# Main_Board.net
KiCad netlist of a schematic drawn in Altium Designer
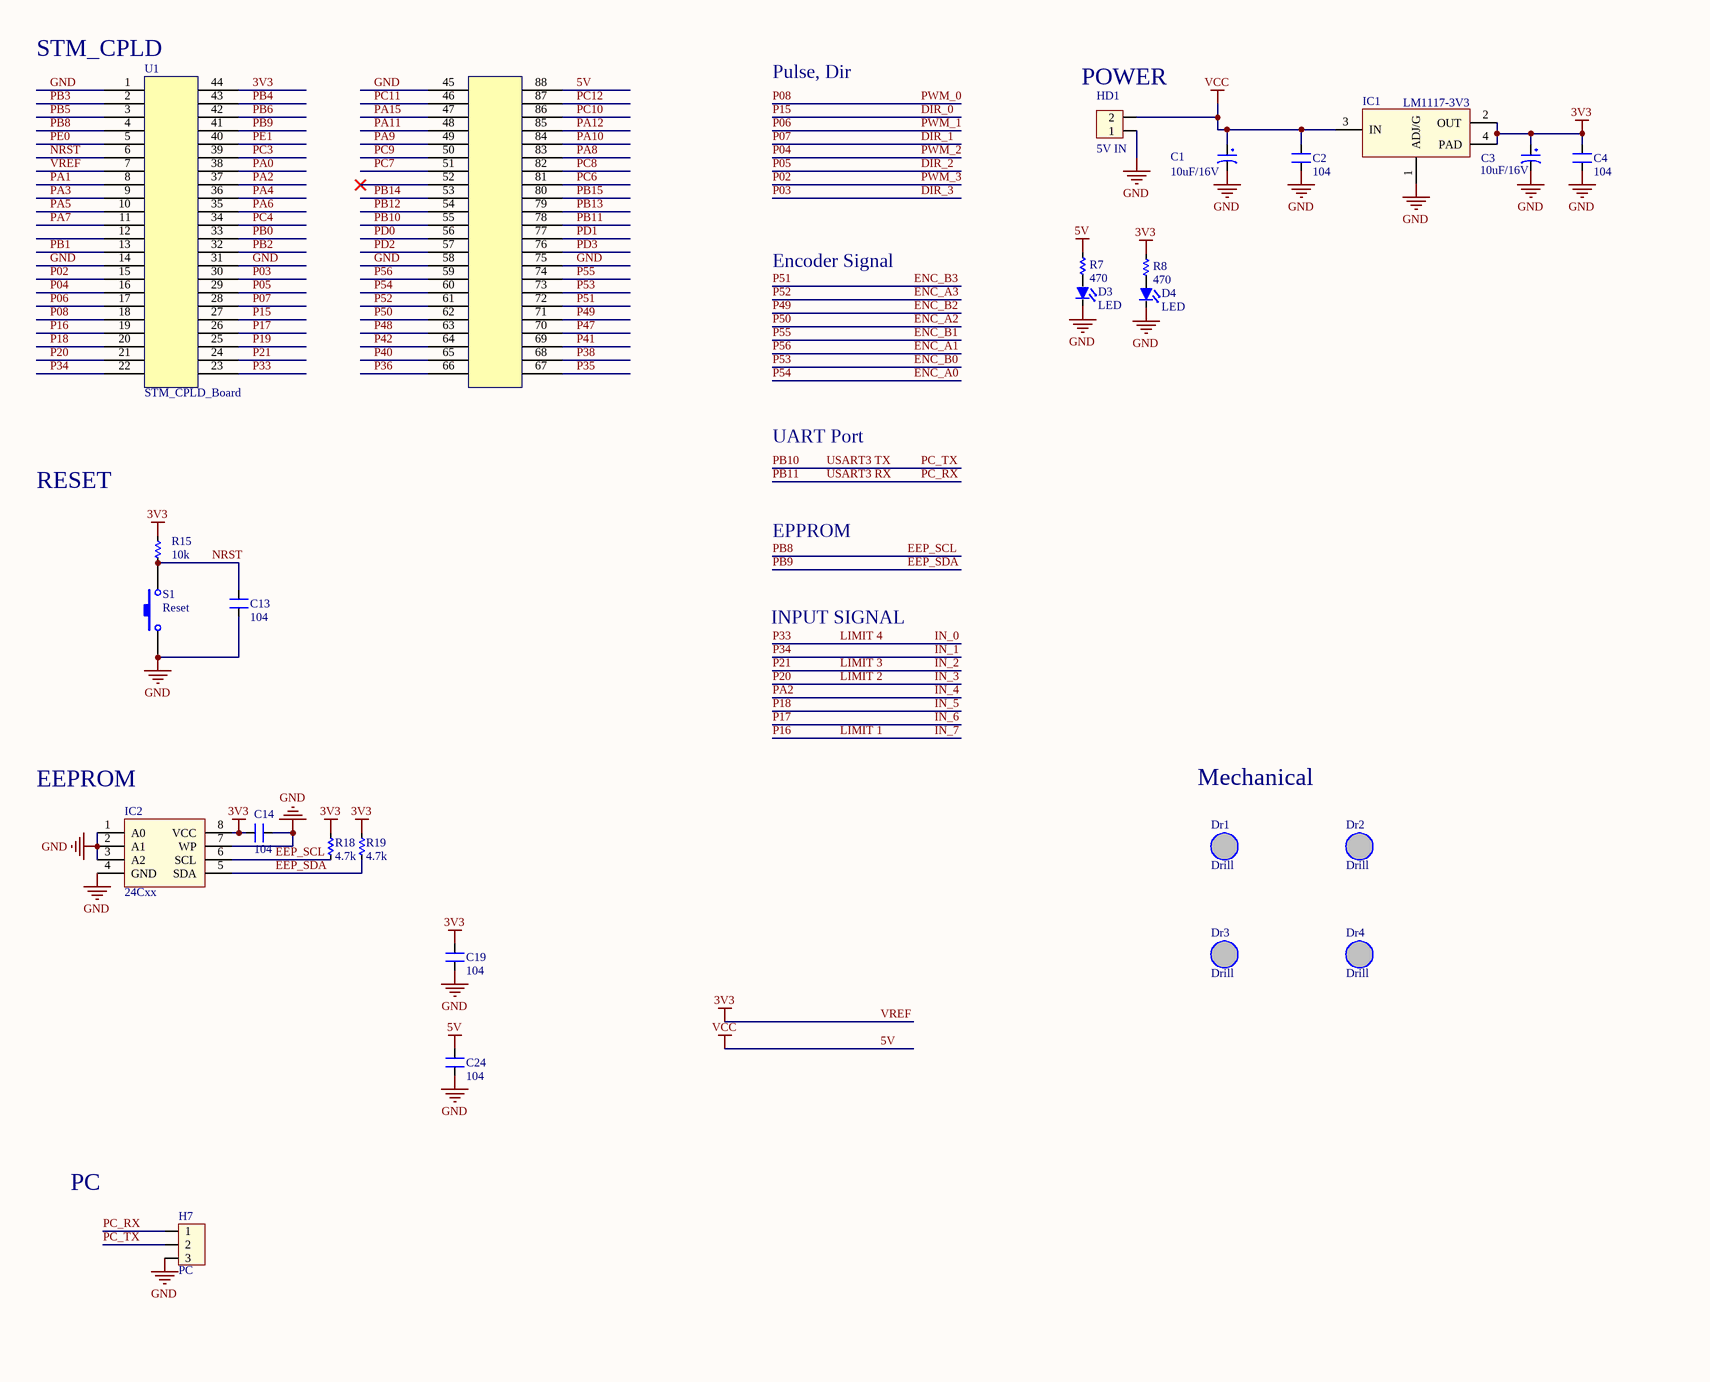
[diagram p0: Main_Board.SchDoc, top left]
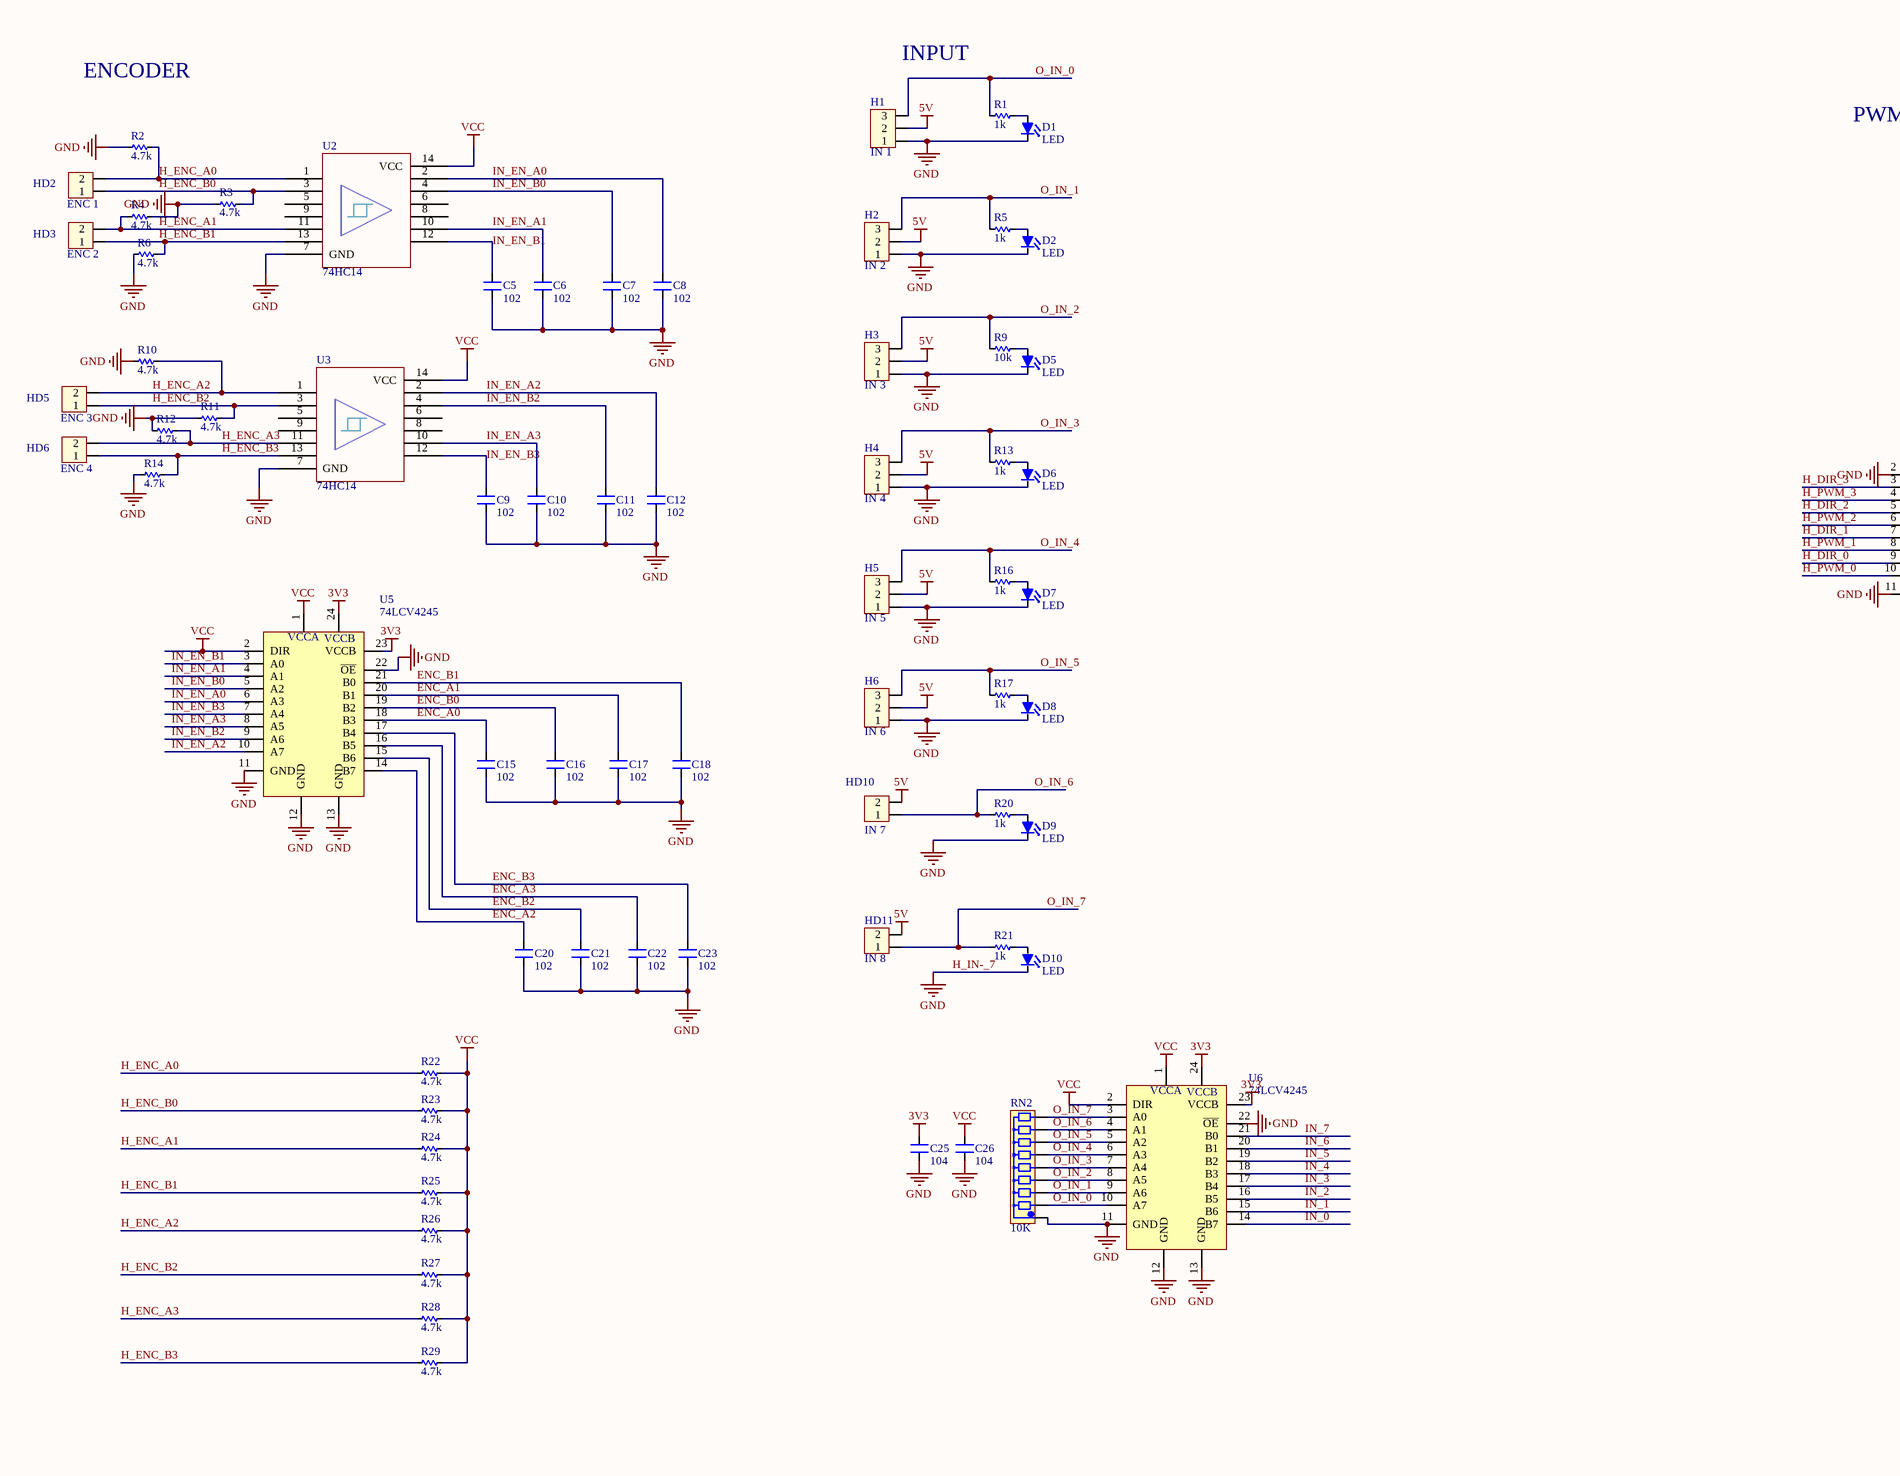
[diagram p1: Main_Board.SchDoc, top middle]
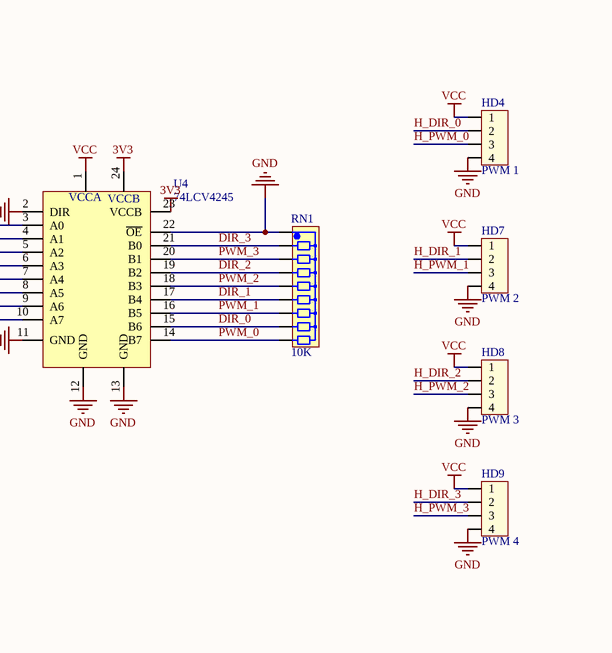
[diagram p2: Main_Board.SchDoc, top right]
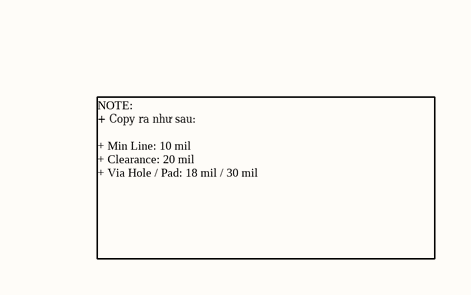
[diagram p3: Main_Board.SchDoc, bottom right]

(export (version "E")
  (design (tool "Eeschema 10.0.6"))
  (components
    (comp (ref "C1")
      (value "10uF/16V")
      (footprint "CAP_ALU_B")
      (description "C 47uF/50V , 220uF/16V")
      (libsource (lib "Main_Board") (part "CP2"))
    )
    (comp (ref "C2")
      (value "104")
      (footprint "CAP-SM-0805")
      (description "Ceramic Capacitor SMD")
      (libsource (lib "Main_Board") (part "CAP_SM_0805"))
    )
    (comp (ref "C3")
      (value "10uF/16V")
      (footprint "CAP_ALU_B")
      (description "C 47uF/50V , 220uF/16V")
      (libsource (lib "Main_Board") (part "CP2"))
    )
    (comp (ref "C4")
      (value "104")
      (footprint "CAP-SM-0805")
      (description "Ceramic Capacitor SMD")
      (libsource (lib "Main_Board") (part "CAP_SM_0805"))
    )
    (comp (ref "C5")
      (value "102")
      (footprint "CAP-SM-0805")
      (description "Ceramic Capacitor SMD")
      (libsource (lib "Main_Board") (part "CAP_SM_0805"))
    )
    (comp (ref "C6")
      (value "102")
      (footprint "CAP-SM-0805")
      (description "Ceramic Capacitor SMD")
      (libsource (lib "Main_Board") (part "CAP_SM_0805"))
    )
    (comp (ref "C7")
      (value "102")
      (footprint "CAP-SM-0805")
      (description "Ceramic Capacitor SMD")
      (libsource (lib "Main_Board") (part "CAP_SM_0805"))
    )
    (comp (ref "C8")
      (value "102")
      (footprint "CAP-SM-0805")
      (description "Ceramic Capacitor SMD")
      (libsource (lib "Main_Board") (part "CAP_SM_0805"))
    )
    (comp (ref "C9")
      (value "102")
      (footprint "CAP-SM-0805")
      (description "Ceramic Capacitor SMD")
      (libsource (lib "Main_Board") (part "CAP_SM_0805"))
    )
    (comp (ref "C10")
      (value "102")
      (footprint "CAP-SM-0805")
      (description "Ceramic Capacitor SMD")
      (libsource (lib "Main_Board") (part "CAP_SM_0805"))
    )
    (comp (ref "C11")
      (value "102")
      (footprint "CAP-SM-0805")
      (description "Ceramic Capacitor SMD")
      (libsource (lib "Main_Board") (part "CAP_SM_0805"))
    )
    (comp (ref "C12")
      (value "102")
      (footprint "CAP-SM-0805")
      (description "Ceramic Capacitor SMD")
      (libsource (lib "Main_Board") (part "CAP_SM_0805"))
    )
    (comp (ref "C13")
      (value "104")
      (footprint "CAP-SM-0805")
      (description "Ceramic Capacitor SMD")
      (libsource (lib "Main_Board") (part "CAP_SM_0805"))
    )
    (comp (ref "C14")
      (value "104")
      (footprint "CAP-SM-0805")
      (description "Ceramic Capacitor SMD")
      (libsource (lib "Main_Board") (part "CAP_SM_0805"))
    )
    (comp (ref "C15")
      (value "102")
      (footprint "CAP-SM-0805")
      (description "Ceramic Capacitor SMD")
      (libsource (lib "Main_Board") (part "CAP_SM_0805"))
    )
    (comp (ref "C16")
      (value "102")
      (footprint "CAP-SM-0805")
      (description "Ceramic Capacitor SMD")
      (libsource (lib "Main_Board") (part "CAP_SM_0805"))
    )
    (comp (ref "C17")
      (value "102")
      (footprint "CAP-SM-0805")
      (description "Ceramic Capacitor SMD")
      (libsource (lib "Main_Board") (part "CAP_SM_0805"))
    )
    (comp (ref "C18")
      (value "102")
      (footprint "CAP-SM-0805")
      (description "Ceramic Capacitor SMD")
      (libsource (lib "Main_Board") (part "CAP_SM_0805"))
    )
    (comp (ref "C19")
      (value "104")
      (footprint "CAP-SM-0805")
      (description "Ceramic Capacitor SMD")
      (libsource (lib "Main_Board") (part "CAP_SM_0805"))
    )
    (comp (ref "C20")
      (value "102")
      (footprint "CAP-SM-0805")
      (description "Ceramic Capacitor SMD")
      (libsource (lib "Main_Board") (part "CAP_SM_0805"))
    )
    (comp (ref "C21")
      (value "102")
      (footprint "CAP-SM-0805")
      (description "Ceramic Capacitor SMD")
      (libsource (lib "Main_Board") (part "CAP_SM_0805"))
    )
    (comp (ref "C22")
      (value "102")
      (footprint "CAP-SM-0805")
      (description "Ceramic Capacitor SMD")
      (libsource (lib "Main_Board") (part "CAP_SM_0805"))
    )
    (comp (ref "C23")
      (value "102")
      (footprint "CAP-SM-0805")
      (description "Ceramic Capacitor SMD")
      (libsource (lib "Main_Board") (part "CAP_SM_0805"))
    )
    (comp (ref "C24")
      (value "104")
      (footprint "CAP-SM-0805")
      (description "Ceramic Capacitor SMD")
      (libsource (lib "Main_Board") (part "CAP_SM_0805"))
    )
    (comp (ref "C25")
      (value "104")
      (footprint "CAP-SM-0805")
      (description "Ceramic Capacitor SMD")
      (libsource (lib "Main_Board") (part "CAP_SM_0805"))
    )
    (comp (ref "C26")
      (value "104")
      (footprint "CAP-SM-0805")
      (description "Ceramic Capacitor SMD")
      (libsource (lib "Main_Board") (part "CAP_SM_0805"))
    )
    (comp (ref "D1")
      (value "LED")
      (footprint "LED_0805_Blue")
      (description "LED SMD")
      (libsource (lib "Main_Board") (part "LED_SMD"))
    )
    (comp (ref "D2")
      (value "LED")
      (footprint "LED_0805_Blue")
      (description "LED SMD")
      (libsource (lib "Main_Board") (part "LED_SMD"))
    )
    (comp (ref "D3")
      (value "LED")
      (footprint "LED_0805_Blue")
      (description "LED SMD")
      (libsource (lib "Main_Board") (part "LED_SMD"))
    )
    (comp (ref "D4")
      (value "LED")
      (footprint "LED_0805_Blue")
      (description "LED SMD")
      (libsource (lib "Main_Board") (part "LED_SMD"))
    )
    (comp (ref "D5")
      (value "LED")
      (footprint "LED_0805_Blue")
      (description "LED SMD")
      (libsource (lib "Main_Board") (part "LED_SMD"))
    )
    (comp (ref "D6")
      (value "LED")
      (footprint "LED_0805_Blue")
      (description "LED SMD")
      (libsource (lib "Main_Board") (part "LED_SMD"))
    )
    (comp (ref "D7")
      (value "LED")
      (footprint "LED_0805_Blue")
      (description "LED SMD")
      (libsource (lib "Main_Board") (part "LED_SMD"))
    )
    (comp (ref "D8")
      (value "LED")
      (footprint "LED_0805_Blue")
      (description "LED SMD")
      (libsource (lib "Main_Board") (part "LED_SMD"))
    )
    (comp (ref "D9")
      (value "LED")
      (footprint "LED_0805_Blue")
      (description "LED SMD")
      (libsource (lib "Main_Board") (part "LED_SMD"))
    )
    (comp (ref "D10")
      (value "LED")
      (footprint "LED_0805_Blue")
      (description "LED SMD")
      (libsource (lib "Main_Board") (part "LED_SMD"))
    )
    (comp (ref "Dr1")
      (value "Drill")
      (footprint "Drill 3mm")
      (description "Drill 3mm")
      (libsource (lib "Main_Board") (part "Drill 3mm"))
    )
    (comp (ref "Dr2")
      (value "Drill")
      (footprint "Drill 3mm")
      (description "Drill 3mm")
      (libsource (lib "Main_Board") (part "Drill 3mm"))
    )
    (comp (ref "Dr3")
      (value "Drill")
      (footprint "Drill 3mm")
      (description "Drill 3mm")
      (libsource (lib "Main_Board") (part "Drill 3mm"))
    )
    (comp (ref "Dr4")
      (value "Drill")
      (footprint "Drill 3mm")
      (description "Drill 3mm")
      (libsource (lib "Main_Board") (part "Drill 3mm"))
    )
    (comp (ref "H1")
      (value "IN 1")
      (footprint "Header White 3")
      (description "Connector 3")
      (libsource (lib "Main_Board") (part "Header white 3"))
    )
    (comp (ref "H2")
      (value "IN 2")
      (footprint "Header White 3")
      (description "Connector 3")
      (libsource (lib "Main_Board") (part "Header white 3"))
    )
    (comp (ref "H3")
      (value "IN 3")
      (footprint "Header White 3")
      (description "Connector 3")
      (libsource (lib "Main_Board") (part "Header white 3"))
    )
    (comp (ref "H4")
      (value "IN 4")
      (footprint "Header White 3")
      (description "Connector 3")
      (libsource (lib "Main_Board") (part "Header white 3"))
    )
    (comp (ref "H5")
      (value "IN 5")
      (footprint "Header White 3")
      (description "Connector 3")
      (libsource (lib "Main_Board") (part "Header white 3"))
    )
    (comp (ref "H6")
      (value "IN 6")
      (footprint "Header White 3")
      (description "Connector 3")
      (libsource (lib "Main_Board") (part "Header white 3"))
    )
    (comp (ref "H7")
      (value "PC")
      (footprint "Header White 3")
      (description "Connector 3")
      (libsource (lib "") (part "Header white 3_1"))
    )
    (comp (ref "HD1")
      (value "5V IN")
      (footprint "Domino 2")
      (description "Domino 2 200mil")
      (libsource (lib "Main_Board") (part "Domino 2"))
    )
    (comp (ref "HD2")
      (value "ENC 1")
      (footprint "Domino 2")
      (description "Domino 2 200mil")
      (libsource (lib "Main_Board") (part "Domino 2"))
    )
    (comp (ref "HD3")
      (value "ENC 2")
      (footprint "Domino 2")
      (description "Domino 2 200mil")
      (libsource (lib "Main_Board") (part "Domino 2"))
    )
    (comp (ref "HD4")
      (value "PWM 1")
      (footprint "Domino 4")
      (description "Domino 4 200mil")
      (libsource (lib "Main_Board") (part "Domino 4"))
    )
    (comp (ref "HD5")
      (value "ENC 3")
      (footprint "Domino 2")
      (description "Domino 2 200mil")
      (libsource (lib "Main_Board") (part "Domino 2"))
    )
    (comp (ref "HD6")
      (value "ENC 4")
      (footprint "Domino 2")
      (description "Domino 2 200mil")
      (libsource (lib "Main_Board") (part "Domino 2"))
    )
    (comp (ref "HD7")
      (value "PWM 2")
      (footprint "Domino 4")
      (description "Domino 4 200mil")
      (libsource (lib "Main_Board") (part "Domino 4"))
    )
    (comp (ref "HD8")
      (value "PWM 3")
      (footprint "Domino 4")
      (description "Domino 4 200mil")
      (libsource (lib "Main_Board") (part "Domino 4"))
    )
    (comp (ref "HD9")
      (value "PWM 4")
      (footprint "Domino 4")
      (description "Domino 4 200mil")
      (libsource (lib "Main_Board") (part "Domino 4"))
    )
    (comp (ref "HD10")
      (value "IN 7")
      (footprint "Domino 2")
      (description "Domino 2 200mil")
      (libsource (lib "Main_Board") (part "Domino 2"))
    )
    (comp (ref "HD11")
      (value "IN 8")
      (footprint "Domino 2")
      (description "Domino 2 200mil")
      (libsource (lib "Main_Board") (part "Domino 2"))
    )
    (comp (ref "IC1")
      (value "LM1117-3V3")
      (footprint "SOT223-4N")
      (description "Available in 1.8V, 2.5V, 2.85V, 3.3V, 5V, and  Adjustable Versions")
      (libsource (lib "Main_Board") (part "LM1117"))
    )
    (comp (ref "IC2")
      (value "24Cxx")
      (footprint "SOIC8")
      (description "Standard 2-Wire Bus Interface Serial EEPROM")
      (fields (field (name "COPYRIGHT BY") "VanDungEvn"))
      (libsource (lib "Main_Board") (part "24Cxx"))
    )
    (comp (ref "R1")
      (value "1k")
      (footprint "RES-SM-0805")
      (description "Resistor")
      (fields
        (field (name "MANUFACTURER") "Generic Components")
        (field (name "PUBLISHER") "Altium Hobart Technology Centre")
      )
      (libsource (lib "Main_Board") (part "Res-SMD"))
    )
    (comp (ref "R2")
      (value "4.7k")
      (footprint "RES-SM-0805")
      (description "Resistor")
      (fields
        (field (name "MANUFACTURER") "Generic Components")
        (field (name "PUBLISHER") "Altium Hobart Technology Centre")
      )
      (libsource (lib "Main_Board") (part "Res-SMD"))
    )
    (comp (ref "R3")
      (value "4.7k")
      (footprint "RES-SM-0805")
      (description "Resistor")
      (fields
        (field (name "MANUFACTURER") "Generic Components")
        (field (name "PUBLISHER") "Altium Hobart Technology Centre")
      )
      (libsource (lib "Main_Board") (part "Res-SMD"))
    )
    (comp (ref "R4")
      (value "4.7k")
      (footprint "RES-SM-0805")
      (description "Resistor")
      (fields
        (field (name "MANUFACTURER") "Generic Components")
        (field (name "PUBLISHER") "Altium Hobart Technology Centre")
      )
      (libsource (lib "Main_Board") (part "Res-SMD"))
    )
    (comp (ref "R5")
      (value "1k")
      (footprint "RES-SM-0805")
      (description "Resistor")
      (fields
        (field (name "MANUFACTURER") "Generic Components")
        (field (name "PUBLISHER") "Altium Hobart Technology Centre")
      )
      (libsource (lib "Main_Board") (part "Res-SMD"))
    )
    (comp (ref "R6")
      (value "4.7k")
      (footprint "RES-SM-0805")
      (description "Resistor")
      (fields
        (field (name "MANUFACTURER") "Generic Components")
        (field (name "PUBLISHER") "Altium Hobart Technology Centre")
      )
      (libsource (lib "Main_Board") (part "Res-SMD"))
    )
    (comp (ref "R7")
      (value "470")
      (footprint "RES-SM-0805")
      (description "Resistor")
      (fields
        (field (name "MANUFACTURER") "Generic Components")
        (field (name "PUBLISHER") "Altium Hobart Technology Centre")
      )
      (libsource (lib "Main_Board") (part "Res-SMD"))
    )
    (comp (ref "R8")
      (value "470")
      (footprint "RES-SM-0805")
      (description "Resistor")
      (fields
        (field (name "MANUFACTURER") "Generic Components")
        (field (name "PUBLISHER") "Altium Hobart Technology Centre")
      )
      (libsource (lib "Main_Board") (part "Res-SMD"))
    )
    (comp (ref "R9")
      (value "10k")
      (footprint "RES-SM-0805")
      (description "Resistor")
      (fields
        (field (name "MANUFACTURER") "Generic Components")
        (field (name "PUBLISHER") "Altium Hobart Technology Centre")
      )
      (libsource (lib "Main_Board") (part "Res-SMD"))
    )
    (comp (ref "R10")
      (value "4.7k")
      (footprint "RES-SM-0805")
      (description "Resistor")
      (fields
        (field (name "MANUFACTURER") "Generic Components")
        (field (name "PUBLISHER") "Altium Hobart Technology Centre")
      )
      (libsource (lib "Main_Board") (part "Res-SMD"))
    )
    (comp (ref "R11")
      (value "4.7k")
      (footprint "RES-SM-0805")
      (description "Resistor")
      (fields
        (field (name "MANUFACTURER") "Generic Components")
        (field (name "PUBLISHER") "Altium Hobart Technology Centre")
      )
      (libsource (lib "Main_Board") (part "Res-SMD"))
    )
    (comp (ref "R12")
      (value "4.7k")
      (footprint "RES-SM-0805")
      (description "Resistor")
      (fields
        (field (name "MANUFACTURER") "Generic Components")
        (field (name "PUBLISHER") "Altium Hobart Technology Centre")
      )
      (libsource (lib "Main_Board") (part "Res-SMD"))
    )
    (comp (ref "R13")
      (value "1k")
      (footprint "RES-SM-0805")
      (description "Resistor")
      (fields
        (field (name "MANUFACTURER") "Generic Components")
        (field (name "PUBLISHER") "Altium Hobart Technology Centre")
      )
      (libsource (lib "Main_Board") (part "Res-SMD"))
    )
    (comp (ref "R14")
      (value "4.7k")
      (footprint "RES-SM-0805")
      (description "Resistor")
      (fields
        (field (name "MANUFACTURER") "Generic Components")
        (field (name "PUBLISHER") "Altium Hobart Technology Centre")
      )
      (libsource (lib "Main_Board") (part "Res-SMD"))
    )
    (comp (ref "R15")
      (value "10k")
      (footprint "RES-SM-0805")
      (description "Resistor")
      (fields
        (field (name "MANUFACTURER") "Generic Components")
        (field (name "PUBLISHER") "Altium Hobart Technology Centre")
      )
      (libsource (lib "Main_Board") (part "Res-SMD"))
    )
    (comp (ref "R16")
      (value "1k")
      (footprint "RES-SM-0805")
      (description "Resistor")
      (fields
        (field (name "MANUFACTURER") "Generic Components")
        (field (name "PUBLISHER") "Altium Hobart Technology Centre")
      )
      (libsource (lib "Main_Board") (part "Res-SMD"))
    )
    (comp (ref "R17")
      (value "1k")
      (footprint "RES-SM-0805")
      (description "Resistor")
      (fields
        (field (name "MANUFACTURER") "Generic Components")
        (field (name "PUBLISHER") "Altium Hobart Technology Centre")
      )
      (libsource (lib "Main_Board") (part "Res-SMD"))
    )
    (comp (ref "R18")
      (value "4.7k")
      (footprint "RES-SM-0805")
      (description "Resistor")
      (fields
        (field (name "MANUFACTURER") "Generic Components")
        (field (name "PUBLISHER") "Altium Hobart Technology Centre")
      )
      (libsource (lib "Main_Board") (part "Res-SMD"))
    )
    (comp (ref "R19")
      (value "4.7k")
      (footprint "RES-SM-0805")
      (description "Resistor")
      (fields
        (field (name "MANUFACTURER") "Generic Components")
        (field (name "PUBLISHER") "Altium Hobart Technology Centre")
      )
      (libsource (lib "Main_Board") (part "Res-SMD"))
    )
    (comp (ref "R20")
      (value "1k")
      (footprint "RES-SM-0805")
      (description "Resistor")
      (fields
        (field (name "MANUFACTURER") "Generic Components")
        (field (name "PUBLISHER") "Altium Hobart Technology Centre")
      )
      (libsource (lib "Main_Board") (part "Res-SMD"))
    )
    (comp (ref "R21")
      (value "1k")
      (footprint "RES-SM-0805")
      (description "Resistor")
      (fields
        (field (name "MANUFACTURER") "Generic Components")
        (field (name "PUBLISHER") "Altium Hobart Technology Centre")
      )
      (libsource (lib "Main_Board") (part "Res-SMD"))
    )
    (comp (ref "R22")
      (value "4.7k")
      (footprint "RES-SM-0805")
      (description "Resistor")
      (fields
        (field (name "MANUFACTURER") "Generic Components")
        (field (name "PUBLISHER") "Altium Hobart Technology Centre")
      )
      (libsource (lib "Main_Board") (part "Res-SMD"))
    )
    (comp (ref "R23")
      (value "4.7k")
      (footprint "RES-SM-0805")
      (description "Resistor")
      (fields
        (field (name "MANUFACTURER") "Generic Components")
        (field (name "PUBLISHER") "Altium Hobart Technology Centre")
      )
      (libsource (lib "Main_Board") (part "Res-SMD"))
    )
    (comp (ref "R24")
      (value "4.7k")
      (footprint "RES-SM-0805")
      (description "Resistor")
      (fields
        (field (name "MANUFACTURER") "Generic Components")
        (field (name "PUBLISHER") "Altium Hobart Technology Centre")
      )
      (libsource (lib "Main_Board") (part "Res-SMD"))
    )
    (comp (ref "R25")
      (value "4.7k")
      (footprint "RES-SM-0805")
      (description "Resistor")
      (fields
        (field (name "MANUFACTURER") "Generic Components")
        (field (name "PUBLISHER") "Altium Hobart Technology Centre")
      )
      (libsource (lib "Main_Board") (part "Res-SMD"))
    )
    (comp (ref "R26")
      (value "4.7k")
      (footprint "RES-SM-0805")
      (description "Resistor")
      (fields
        (field (name "MANUFACTURER") "Generic Components")
        (field (name "PUBLISHER") "Altium Hobart Technology Centre")
      )
      (libsource (lib "Main_Board") (part "Res-SMD"))
    )
    (comp (ref "R27")
      (value "4.7k")
      (footprint "RES-SM-0805")
      (description "Resistor")
      (fields
        (field (name "MANUFACTURER") "Generic Components")
        (field (name "PUBLISHER") "Altium Hobart Technology Centre")
      )
      (libsource (lib "Main_Board") (part "Res-SMD"))
    )
    (comp (ref "R28")
      (value "4.7k")
      (footprint "RES-SM-0805")
      (description "Resistor")
      (fields
        (field (name "MANUFACTURER") "Generic Components")
        (field (name "PUBLISHER") "Altium Hobart Technology Centre")
      )
      (libsource (lib "Main_Board") (part "Res-SMD"))
    )
    (comp (ref "R29")
      (value "4.7k")
      (footprint "RES-SM-0805")
      (description "Resistor")
      (fields
        (field (name "MANUFACTURER") "Generic Components")
        (field (name "PUBLISHER") "Altium Hobart Technology Centre")
      )
      (libsource (lib "Main_Board") (part "Res-SMD"))
    )
    (comp (ref "RN1")
      (value "10K")
      (footprint "RN8")
      (description "Resistor 8 (Thanh)")
      (libsource (lib "Main_Board") (part "RN8"))
    )
    (comp (ref "RN2")
      (value "10K")
      (footprint "RN8")
      (description "Resistor 8 (Thanh)")
      (libsource (lib "") (part "RN8_1"))
    )
    (comp (ref "S1")
      (value "Reset")
      (footprint "SW2")
      (description "Switch button 2 pin")
      (libsource (lib "Main_Board") (part "SW - 2Pin"))
    )
    (comp (ref "U1")
      (value "STM_CPLD_Board")
      (footprint "STM_CPLD_Board")
      (description "STM32f4 and Max2 570 on one board")
      (libsource (lib "Main_Board") (part "STM_CPLD_Board"))
    )
    (comp (ref "U2")
      (value "74HC14")
      (footprint "SO14-150mil")
      (description "Hex Inverters With SCHMITT-TRIGGER Inputs")
      (libsource (lib "Main_Board") (part "74HC14"))
    )
    (comp (ref "U3")
      (value "74HC14")
      (footprint "SO14-150mil")
      (description "Hex Inverters With SCHMITT-TRIGGER Inputs")
      (libsource (lib "Main_Board") (part "74HC14"))
    )
    (comp (ref "U4")
      (value "74LCV4245")
      (footprint "SOIC24 - wide")
      (description "Octal dual supply translating transceiver; 3-state")
      (libsource (lib "Main_Board") (part "74LCV4245"))
    )
    (comp (ref "U5")
      (value "74LCV4245")
      (footprint "SOIC24 - wide")
      (description "Octal dual supply translating transceiver; 3-state")
      (libsource (lib "Main_Board") (part "74LCV4245"))
    )
    (comp (ref "U6")
      (value "74LCV4245")
      (footprint "SOIC24 - wide")
      (description "Octal dual supply translating transceiver; 3-state")
      (libsource (lib "Main_Board") (part "74LCV4245"))
    )
  )
  (nets
    (net (code "1") (name "/DIR_0") (class "Default")
      (node (ref "RN1") (pin "8") (pinfunction "8_8") (pintype "passive"))
      (node (ref "U1") (pin "27") (pinfunction "27_27") (pintype "passive"))
      (node (ref "U4") (pin "15") (pinfunction "B6_15") (pintype "passive"))
    )
    (net (code "2") (name "/DIR_1") (class "Default")
      (node (ref "RN1") (pin "6") (pinfunction "6_6") (pintype "passive"))
      (node (ref "U1") (pin "28") (pinfunction "28_28") (pintype "passive"))
      (node (ref "U4") (pin "17") (pinfunction "B4_17") (pintype "passive"))
    )
    (net (code "3") (name "/DIR_2") (class "Default")
      (node (ref "RN1") (pin "4") (pinfunction "4_4") (pintype "passive"))
      (node (ref "U1") (pin "29") (pinfunction "29_29") (pintype "passive"))
      (node (ref "U4") (pin "19") (pinfunction "B2_19") (pintype "passive"))
    )
    (net (code "4") (name "/DIR_3") (class "Default")
      (node (ref "RN1") (pin "2") (pinfunction "2_2") (pintype "passive"))
      (node (ref "U1") (pin "30") (pinfunction "30_30") (pintype "passive"))
      (node (ref "U4") (pin "21") (pinfunction "B0_21") (pintype "passive"))
    )
    (net (code "5") (name "/EEP_SCL") (class "Default")
      (node (ref "IC2") (pin "6") (pinfunction "SCL_6") (pintype "passive"))
      (node (ref "R18") (pin "1") (pinfunction "1_1") (pintype "passive"))
      (node (ref "U1") (pin "4") (pinfunction "4_4") (pintype "passive"))
    )
    (net (code "6") (name "/EEP_SDA") (class "Default")
      (node (ref "IC2") (pin "5") (pinfunction "SDA_5") (pintype "passive"))
      (node (ref "R19") (pin "2") (pinfunction "2_2") (pintype "passive"))
      (node (ref "U1") (pin "41") (pinfunction "41_41") (pintype "passive"))
    )
    (net (code "7") (name "/ENC_A0") (class "Default")
      (node (ref "C15") (pin "2") (pinfunction "2_2") (pintype "passive"))
      (node (ref "U1") (pin "60") (pinfunction "60_60") (pintype "passive"))
      (node (ref "U5") (pin "18") (pinfunction "B3_18") (pintype "passive"))
    )
    (net (code "8") (name "/ENC_A1") (class "Default")
      (node (ref "C17") (pin "2") (pinfunction "2_2") (pintype "passive"))
      (node (ref "U1") (pin "59") (pinfunction "59_59") (pintype "passive"))
      (node (ref "U5") (pin "20") (pinfunction "B1_20") (pintype "passive"))
    )
    (net (code "9") (name "/ENC_A2") (class "Default")
      (node (ref "C20") (pin "2") (pinfunction "2_2") (pintype "passive"))
      (node (ref "U1") (pin "62") (pinfunction "62_62") (pintype "passive"))
      (node (ref "U5") (pin "14") (pinfunction "B7_14") (pintype "passive"))
    )
    (net (code "10") (name "/ENC_A3") (class "Default")
      (node (ref "C22") (pin "2") (pinfunction "2_2") (pintype "passive"))
      (node (ref "U1") (pin "61") (pinfunction "61_61") (pintype "passive"))
      (node (ref "U5") (pin "16") (pinfunction "B5_16") (pintype "passive"))
    )
    (net (code "11") (name "/ENC_B0") (class "Default")
      (node (ref "C16") (pin "2") (pinfunction "2_2") (pintype "passive"))
      (node (ref "U1") (pin "73") (pinfunction "73_73") (pintype "passive"))
      (node (ref "U5") (pin "19") (pinfunction "B2_19") (pintype "passive"))
    )
    (net (code "12") (name "/ENC_B1") (class "Default")
      (node (ref "C18") (pin "2") (pinfunction "2_2") (pintype "passive"))
      (node (ref "U1") (pin "74") (pinfunction "74_74") (pintype "passive"))
      (node (ref "U5") (pin "21") (pinfunction "B0_21") (pintype "passive"))
    )
    (net (code "13") (name "/ENC_B2") (class "Default")
      (node (ref "C21") (pin "2") (pinfunction "2_2") (pintype "passive"))
      (node (ref "U1") (pin "71") (pinfunction "71_71") (pintype "passive"))
      (node (ref "U5") (pin "15") (pinfunction "B6_15") (pintype "passive"))
    )
    (net (code "14") (name "/ENC_B3") (class "Default")
      (node (ref "C23") (pin "2") (pinfunction "2_2") (pintype "passive"))
      (node (ref "U1") (pin "72") (pinfunction "72_72") (pintype "passive"))
      (node (ref "U5") (pin "17") (pinfunction "B4_17") (pintype "passive"))
    )
    (net (code "15") (name "/H_DIR_0") (class "Default")
      (node (ref "HD4") (pin "2") (pinfunction "2_2") (pintype "passive"))
      (node (ref "U4") (pin "9") (pinfunction "A6_9") (pintype "passive"))
    )
    (net (code "16") (name "/H_DIR_1") (class "Default")
      (node (ref "HD7") (pin "2") (pinfunction "2_2") (pintype "passive"))
      (node (ref "U4") (pin "7") (pinfunction "A4_7") (pintype "passive"))
    )
    (net (code "17") (name "/H_DIR_2") (class "Default")
      (node (ref "HD8") (pin "2") (pinfunction "2_2") (pintype "passive"))
      (node (ref "U4") (pin "5") (pinfunction "A2_5") (pintype "passive"))
    )
    (net (code "18") (name "/H_DIR_3") (class "Default")
      (node (ref "HD9") (pin "2") (pinfunction "2_2") (pintype "passive"))
      (node (ref "U4") (pin "3") (pinfunction "A0_3") (pintype "passive"))
    )
    (net (code "19") (name "/H_ENC_A0") (class "Default")
      (node (ref "HD2") (pin "2") (pinfunction "2_2") (pintype "passive"))
      (node (ref "R2") (pin "1") (pinfunction "1_1") (pintype "passive"))
      (node (ref "R22") (pin "1") (pinfunction "1_1") (pintype "passive"))
      (node (ref "U2") (pin "1") (pintype "passive"))
    )
    (net (code "20") (name "/H_ENC_A1") (class "Default")
      (node (ref "HD3") (pin "2") (pinfunction "2_2") (pintype "passive"))
      (node (ref "R24") (pin "1") (pinfunction "1_1") (pintype "passive"))
      (node (ref "R4") (pin "2") (pinfunction "2_2") (pintype "passive"))
      (node (ref "U2") (pin "11") (pinfunction "10_11") (pintype "passive"))
    )
    (net (code "21") (name "/H_ENC_A2") (class "Default")
      (node (ref "HD5") (pin "2") (pinfunction "2_2") (pintype "passive"))
      (node (ref "R10") (pin "1") (pinfunction "1_1") (pintype "passive"))
      (node (ref "R26") (pin "1") (pinfunction "1_1") (pintype "passive"))
      (node (ref "U3") (pin "1") (pintype "passive"))
    )
    (net (code "22") (name "/H_ENC_A3") (class "Default")
      (node (ref "HD6") (pin "2") (pinfunction "2_2") (pintype "passive"))
      (node (ref "R12") (pin "1") (pinfunction "1_1") (pintype "passive"))
      (node (ref "R28") (pin "1") (pinfunction "1_1") (pintype "passive"))
      (node (ref "U3") (pin "11") (pinfunction "10_11") (pintype "passive"))
    )
    (net (code "23") (name "/H_ENC_B0") (class "Default")
      (node (ref "HD2") (pin "1") (pinfunction "1_1") (pintype "passive"))
      (node (ref "R23") (pin "1") (pinfunction "1_1") (pintype "passive"))
      (node (ref "R3") (pin "1") (pinfunction "1_1") (pintype "passive"))
      (node (ref "U2") (pin "3") (pintype "passive"))
    )
    (net (code "24") (name "/H_ENC_B1") (class "Default")
      (node (ref "HD3") (pin "1") (pinfunction "1_1") (pintype "passive"))
      (node (ref "R25") (pin "1") (pinfunction "1_1") (pintype "passive"))
      (node (ref "R6") (pin "1") (pinfunction "1_1") (pintype "passive"))
      (node (ref "U2") (pin "13") (pinfunction "12_13") (pintype "passive"))
    )
    (net (code "25") (name "/H_ENC_B2") (class "Default")
      (node (ref "HD5") (pin "1") (pinfunction "1_1") (pintype "passive"))
      (node (ref "R11") (pin "1") (pinfunction "1_1") (pintype "passive"))
      (node (ref "R27") (pin "1") (pinfunction "1_1") (pintype "passive"))
      (node (ref "U3") (pin "3") (pintype "passive"))
    )
    (net (code "26") (name "/H_ENC_B3") (class "Default")
      (node (ref "HD6") (pin "1") (pinfunction "1_1") (pintype "passive"))
      (node (ref "R14") (pin "1") (pinfunction "1_1") (pintype "passive"))
      (node (ref "R29") (pin "1") (pinfunction "1_1") (pintype "passive"))
      (node (ref "U3") (pin "13") (pinfunction "12_13") (pintype "passive"))
    )
    (net (code "27") (name "/H_PWM_0") (class "Default")
      (node (ref "HD4") (pin "3") (pinfunction "3_3") (pintype "passive"))
      (node (ref "U4") (pin "10") (pinfunction "A7_10") (pintype "passive"))
    )
    (net (code "28") (name "/H_PWM_1") (class "Default")
      (node (ref "HD7") (pin "3") (pinfunction "3_3") (pintype "passive"))
      (node (ref "U4") (pin "8") (pinfunction "A5_8") (pintype "passive"))
    )
    (net (code "29") (name "/H_PWM_2") (class "Default")
      (node (ref "HD8") (pin "3") (pinfunction "3_3") (pintype "passive"))
      (node (ref "U4") (pin "6") (pinfunction "A3_6") (pintype "passive"))
    )
    (net (code "30") (name "/H_PWM_3") (class "Default")
      (node (ref "HD9") (pin "3") (pinfunction "3_3") (pintype "passive"))
      (node (ref "U4") (pin "4") (pinfunction "A1_4") (pintype "passive"))
    )
    (net (code "31") (name "/IN_0") (class "Default")
      (node (ref "U1") (pin "23") (pinfunction "23_23") (pintype "passive"))
      (node (ref "U6") (pin "14") (pinfunction "B7_14") (pintype "passive"))
    )
    (net (code "32") (name "/IN_1") (class "Default")
      (node (ref "U1") (pin "22") (pinfunction "22_22") (pintype "passive"))
      (node (ref "U6") (pin "15") (pinfunction "B6_15") (pintype "passive"))
    )
    (net (code "33") (name "/IN_2") (class "Default")
      (node (ref "U1") (pin "24") (pinfunction "24_24") (pintype "passive"))
      (node (ref "U6") (pin "16") (pinfunction "B5_16") (pintype "passive"))
    )
    (net (code "34") (name "/IN_3") (class "Default")
      (node (ref "U1") (pin "21") (pinfunction "21_21") (pintype "passive"))
      (node (ref "U6") (pin "17") (pinfunction "B4_17") (pintype "passive"))
    )
    (net (code "35") (name "/IN_4") (class "Default")
      (node (ref "U1") (pin "37") (pinfunction "37_37") (pintype "passive"))
      (node (ref "U6") (pin "18") (pinfunction "B3_18") (pintype "passive"))
    )
    (net (code "36") (name "/IN_5") (class "Default")
      (node (ref "U1") (pin "20") (pinfunction "20_20") (pintype "passive"))
      (node (ref "U6") (pin "19") (pinfunction "B2_19") (pintype "passive"))
    )
    (net (code "37") (name "/IN_6") (class "Default")
      (node (ref "U1") (pin "26") (pinfunction "26_26") (pintype "passive"))
      (node (ref "U6") (pin "20") (pinfunction "B1_20") (pintype "passive"))
    )
    (net (code "38") (name "/IN_7") (class "Default")
      (node (ref "U1") (pin "19") (pinfunction "19_19") (pintype "passive"))
      (node (ref "U6") (pin "21") (pinfunction "B0_21") (pintype "passive"))
    )
    (net (code "39") (name "/IN_EN_A0") (class "Default")
      (node (ref "C8") (pin "2") (pinfunction "2_2") (pintype "passive"))
      (node (ref "U2") (pin "2") (pintype "passive"))
      (node (ref "U5") (pin "6") (pinfunction "A3_6") (pintype "passive"))
    )
    (net (code "40") (name "/IN_EN_A1") (class "Default")
      (node (ref "C6") (pin "2") (pinfunction "2_2") (pintype "passive"))
      (node (ref "U2") (pin "10") (pinfunction "9_10") (pintype "passive"))
      (node (ref "U5") (pin "4") (pinfunction "A1_4") (pintype "passive"))
    )
    (net (code "41") (name "/IN_EN_A2") (class "Default")
      (node (ref "C12") (pin "2") (pinfunction "2_2") (pintype "passive"))
      (node (ref "U3") (pin "2") (pintype "passive"))
      (node (ref "U5") (pin "10") (pinfunction "A7_10") (pintype "passive"))
    )
    (net (code "42") (name "/IN_EN_A3") (class "Default")
      (node (ref "C10") (pin "2") (pinfunction "2_2") (pintype "passive"))
      (node (ref "U3") (pin "10") (pinfunction "9_10") (pintype "passive"))
      (node (ref "U5") (pin "8") (pinfunction "A5_8") (pintype "passive"))
    )
    (net (code "43") (name "/IN_EN_B0") (class "Default")
      (node (ref "C7") (pin "2") (pinfunction "2_2") (pintype "passive"))
      (node (ref "U2") (pin "4") (pintype "passive"))
      (node (ref "U5") (pin "5") (pinfunction "A2_5") (pintype "passive"))
    )
    (net (code "44") (name "/IN_EN_B1") (class "Default")
      (node (ref "C5") (pin "2") (pinfunction "2_2") (pintype "passive"))
      (node (ref "U2") (pin "12") (pinfunction "11_12") (pintype "passive"))
      (node (ref "U5") (pin "3") (pinfunction "A0_3") (pintype "passive"))
    )
    (net (code "45") (name "/IN_EN_B2") (class "Default")
      (node (ref "C11") (pin "2") (pinfunction "2_2") (pintype "passive"))
      (node (ref "U3") (pin "4") (pintype "passive"))
      (node (ref "U5") (pin "9") (pinfunction "A6_9") (pintype "passive"))
    )
    (net (code "46") (name "/IN_EN_B3") (class "Default")
      (node (ref "C9") (pin "2") (pinfunction "2_2") (pintype "passive"))
      (node (ref "U3") (pin "12") (pinfunction "11_12") (pintype "passive"))
      (node (ref "U5") (pin "7") (pinfunction "A4_7") (pintype "passive"))
    )
    (net (code "47") (name "/NRST") (class "Default")
      (node (ref "C13") (pin "1") (pinfunction "1_1") (pintype "passive"))
      (node (ref "R15") (pin "2") (pinfunction "2_2") (pintype "passive"))
      (node (ref "S1") (pin "2") (pinfunction "2_2") (pintype "passive"))
      (node (ref "U1") (pin "6") (pinfunction "6_6") (pintype "passive"))
    )
    (net (code "48") (name "/O_IN_0") (class "Default")
      (node (ref "H1") (pin "3") (pinfunction "3_3") (pintype "passive"))
      (node (ref "R1") (pin "2") (pinfunction "2_2") (pintype "passive"))
      (node (ref "RN2") (pin "2") (pinfunction "2_2") (pintype "passive"))
      (node (ref "U6") (pin "10") (pinfunction "A7_10") (pintype "passive"))
    )
    (net (code "49") (name "/O_IN_1") (class "Default")
      (node (ref "H2") (pin "3") (pinfunction "3_3") (pintype "passive"))
      (node (ref "R5") (pin "2") (pinfunction "2_2") (pintype "passive"))
      (node (ref "RN2") (pin "3") (pinfunction "3_3") (pintype "passive"))
      (node (ref "U6") (pin "9") (pinfunction "A6_9") (pintype "passive"))
    )
    (net (code "50") (name "/O_IN_2") (class "Default")
      (node (ref "H3") (pin "3") (pinfunction "3_3") (pintype "passive"))
      (node (ref "R9") (pin "2") (pinfunction "2_2") (pintype "passive"))
      (node (ref "RN2") (pin "4") (pinfunction "4_4") (pintype "passive"))
      (node (ref "U6") (pin "8") (pinfunction "A5_8") (pintype "passive"))
    )
    (net (code "51") (name "/O_IN_3") (class "Default")
      (node (ref "H4") (pin "3") (pinfunction "3_3") (pintype "passive"))
      (node (ref "R13") (pin "2") (pinfunction "2_2") (pintype "passive"))
      (node (ref "RN2") (pin "5") (pinfunction "5_5") (pintype "passive"))
      (node (ref "U6") (pin "7") (pinfunction "A4_7") (pintype "passive"))
    )
    (net (code "52") (name "/O_IN_4") (class "Default")
      (node (ref "H5") (pin "3") (pinfunction "3_3") (pintype "passive"))
      (node (ref "R16") (pin "2") (pinfunction "2_2") (pintype "passive"))
      (node (ref "RN2") (pin "6") (pinfunction "6_6") (pintype "passive"))
      (node (ref "U6") (pin "6") (pinfunction "A3_6") (pintype "passive"))
    )
    (net (code "53") (name "/O_IN_5") (class "Default")
      (node (ref "H6") (pin "3") (pinfunction "3_3") (pintype "passive"))
      (node (ref "R17") (pin "2") (pinfunction "2_2") (pintype "passive"))
      (node (ref "RN2") (pin "7") (pinfunction "7_7") (pintype "passive"))
      (node (ref "U6") (pin "5") (pinfunction "A2_5") (pintype "passive"))
    )
    (net (code "54") (name "/O_IN_6") (class "Default")
      (node (ref "HD10") (pin "1") (pinfunction "1_1") (pintype "passive"))
      (node (ref "R20") (pin "2") (pinfunction "2_2") (pintype "passive"))
      (node (ref "RN2") (pin "8") (pinfunction "8_8") (pintype "passive"))
      (node (ref "U6") (pin "4") (pinfunction "A1_4") (pintype "passive"))
    )
    (net (code "55") (name "/O_IN_7") (class "Default")
      (node (ref "HD11") (pin "1") (pinfunction "1_1") (pintype "passive"))
      (node (ref "R21") (pin "2") (pinfunction "2_2") (pintype "passive"))
      (node (ref "RN2") (pin "9") (pinfunction "9_9") (pintype "passive"))
      (node (ref "U6") (pin "3") (pinfunction "A0_3") (pintype "passive"))
    )
    (net (code "56") (name "/P02") (class "Default")
      (node (ref "RN1") (pin "3") (pinfunction "3_3") (pintype "passive"))
      (node (ref "U1") (pin "15") (pinfunction "15_15") (pintype "passive"))
      (node (ref "U4") (pin "20") (pinfunction "B1_20") (pintype "passive"))
    )
    (net (code "57") (name "/P04") (class "Default")
      (node (ref "RN1") (pin "5") (pinfunction "5_5") (pintype "passive"))
      (node (ref "U1") (pin "16") (pinfunction "16_16") (pintype "passive"))
      (node (ref "U4") (pin "18") (pinfunction "B3_18") (pintype "passive"))
    )
    (net (code "58") (name "/P06") (class "Default")
      (node (ref "RN1") (pin "7") (pinfunction "7_7") (pintype "passive"))
      (node (ref "U1") (pin "17") (pinfunction "17_17") (pintype "passive"))
      (node (ref "U4") (pin "16") (pinfunction "B5_16") (pintype "passive"))
    )
    (net (code "59") (name "/P08") (class "Default")
      (node (ref "RN1") (pin "9") (pinfunction "9_9") (pintype "passive"))
      (node (ref "U1") (pin "18") (pinfunction "18_18") (pintype "passive"))
      (node (ref "U4") (pin "14") (pinfunction "B7_14") (pintype "passive"))
    )
    (net (code "60") (name "/P19") (class "Default")
      (node (ref "U1") (pin "25") (pinfunction "25_25") (pintype "passive"))
    )
    (net (code "61") (name "/P35") (class "Default")
      (node (ref "U1") (pin "67") (pinfunction "67_67") (pintype "passive"))
    )
    (net (code "62") (name "/P36") (class "Default")
      (node (ref "U1") (pin "66") (pinfunction "66_66") (pintype "passive"))
    )
    (net (code "63") (name "/P38") (class "Default")
      (node (ref "U1") (pin "68") (pinfunction "68_68") (pintype "passive"))
    )
    (net (code "64") (name "/P40") (class "Default")
      (node (ref "U1") (pin "65") (pinfunction "65_65") (pintype "passive"))
    )
    (net (code "65") (name "/P41") (class "Default")
      (node (ref "U1") (pin "69") (pinfunction "69_69") (pintype "passive"))
    )
    (net (code "66") (name "/P42") (class "Default")
      (node (ref "U1") (pin "64") (pinfunction "64_64") (pintype "passive"))
    )
    (net (code "67") (name "/P47") (class "Default")
      (node (ref "U1") (pin "70") (pinfunction "70_70") (pintype "passive"))
    )
    (net (code "68") (name "/P48") (class "Default")
      (node (ref "U1") (pin "63") (pinfunction "63_63") (pintype "passive"))
    )
    (net (code "69") (name "/PA0") (class "Default")
      (node (ref "U1") (pin "38") (pinfunction "38_38") (pintype "passive"))
    )
    (net (code "70") (name "/PA1") (class "Default")
      (node (ref "U1") (pin "8") (pinfunction "8_8") (pintype "passive"))
    )
    (net (code "71") (name "/PA3") (class "Default")
      (node (ref "U1") (pin "9") (pinfunction "9_9") (pintype "passive"))
    )
    (net (code "72") (name "/PA4") (class "Default")
      (node (ref "U1") (pin "36") (pinfunction "36_36") (pintype "passive"))
    )
    (net (code "73") (name "/PA5") (class "Default")
      (node (ref "U1") (pin "10") (pinfunction "10_10") (pintype "passive"))
    )
    (net (code "74") (name "/PA6") (class "Default")
      (node (ref "U1") (pin "35") (pinfunction "35_35") (pintype "passive"))
    )
    (net (code "75") (name "/PA7") (class "Default")
      (node (ref "U1") (pin "11") (pinfunction "11_11") (pintype "passive"))
    )
    (net (code "76") (name "/PA8") (class "Default")
      (node (ref "U1") (pin "83") (pinfunction "83_83") (pintype "passive"))
    )
    (net (code "77") (name "/PA9") (class "Default")
      (node (ref "U1") (pin "49") (pinfunction "49_49") (pintype "passive"))
    )
    (net (code "78") (name "/PA10") (class "Default")
      (node (ref "U1") (pin "84") (pinfunction "84_84") (pintype "passive"))
    )
    (net (code "79") (name "/PA11") (class "Default")
      (node (ref "U1") (pin "48") (pinfunction "48_48") (pintype "passive"))
    )
    (net (code "80") (name "/PA12") (class "Default")
      (node (ref "U1") (pin "85") (pinfunction "85_85") (pintype "passive"))
    )
    (net (code "81") (name "/PA15") (class "Default")
      (node (ref "U1") (pin "47") (pinfunction "47_47") (pintype "passive"))
    )
    (net (code "82") (name "/PB0") (class "Default")
      (node (ref "U1") (pin "33") (pinfunction "33_33") (pintype "passive"))
    )
    (net (code "83") (name "/PB1") (class "Default")
      (node (ref "U1") (pin "13") (pinfunction "13_13") (pintype "passive"))
    )
    (net (code "84") (name "/PB2") (class "Default")
      (node (ref "U1") (pin "32") (pinfunction "32_32") (pintype "passive"))
    )
    (net (code "85") (name "/PB3") (class "Default")
      (node (ref "U1") (pin "2") (pinfunction "2_2") (pintype "passive"))
    )
    (net (code "86") (name "/PB4") (class "Default")
      (node (ref "U1") (pin "43") (pinfunction "43_43") (pintype "passive"))
    )
    (net (code "87") (name "/PB5") (class "Default")
      (node (ref "U1") (pin "3") (pinfunction "3_3") (pintype "passive"))
    )
    (net (code "88") (name "/PB6") (class "Default")
      (node (ref "U1") (pin "42") (pinfunction "42_42") (pintype "passive"))
    )
    (net (code "89") (name "/PB10") (class "Default")
      (node (ref "H7") (pin "2") (pinfunction "2_2") (pintype "passive"))
      (node (ref "U1") (pin "55") (pinfunction "55_55") (pintype "passive"))
    )
    (net (code "90") (name "/PB11") (class "Default")
      (node (ref "H7") (pin "1") (pinfunction "1_1") (pintype "passive"))
      (node (ref "U1") (pin "78") (pinfunction "78_78") (pintype "passive"))
    )
    (net (code "91") (name "/PB12") (class "Default")
      (node (ref "U1") (pin "54") (pinfunction "54_54") (pintype "passive"))
    )
    (net (code "92") (name "/PB13") (class "Default")
      (node (ref "U1") (pin "79") (pinfunction "79_79") (pintype "passive"))
    )
    (net (code "93") (name "/PB14") (class "Default")
      (node (ref "U1") (pin "53") (pinfunction "53_53") (pintype "passive"))
    )
    (net (code "94") (name "/PB15") (class "Default")
      (node (ref "U1") (pin "80") (pinfunction "80_80") (pintype "passive"))
    )
    (net (code "95") (name "/PC3") (class "Default")
      (node (ref "U1") (pin "39") (pinfunction "39_39") (pintype "passive"))
    )
    (net (code "96") (name "/PC4") (class "Default")
      (node (ref "U1") (pin "34") (pinfunction "34_34") (pintype "passive"))
    )
    (net (code "97") (name "/PC6") (class "Default")
      (node (ref "U1") (pin "81") (pinfunction "81_81") (pintype "passive"))
    )
    (net (code "98") (name "/PC7") (class "Default")
      (node (ref "U1") (pin "51") (pinfunction "51_51") (pintype "passive"))
    )
    (net (code "99") (name "/PC8") (class "Default")
      (node (ref "U1") (pin "82") (pinfunction "82_82") (pintype "passive"))
    )
    (net (code "100") (name "/PC9") (class "Default")
      (node (ref "U1") (pin "50") (pinfunction "50_50") (pintype "passive"))
    )
    (net (code "101") (name "/PC10") (class "Default")
      (node (ref "U1") (pin "86") (pinfunction "86_86") (pintype "passive"))
    )
    (net (code "102") (name "/PC11") (class "Default")
      (node (ref "U1") (pin "46") (pinfunction "46_46") (pintype "passive"))
    )
    (net (code "103") (name "/PC12") (class "Default")
      (node (ref "U1") (pin "87") (pinfunction "87_87") (pintype "passive"))
    )
    (net (code "104") (name "/PD0") (class "Default")
      (node (ref "U1") (pin "56") (pinfunction "56_56") (pintype "passive"))
    )
    (net (code "105") (name "/PD1") (class "Default")
      (node (ref "U1") (pin "77") (pinfunction "77_77") (pintype "passive"))
    )
    (net (code "106") (name "/PD2") (class "Default")
      (node (ref "U1") (pin "57") (pinfunction "57_57") (pintype "passive"))
    )
    (net (code "107") (name "/PD3") (class "Default")
      (node (ref "U1") (pin "76") (pinfunction "76_76") (pintype "passive"))
    )
    (net (code "108") (name "/PE0") (class "Default")
      (node (ref "U1") (pin "5") (pinfunction "5_5") (pintype "passive"))
    )
    (net (code "109") (name "/PE1") (class "Default")
      (node (ref "U1") (pin "40") (pinfunction "40_40") (pintype "passive"))
    )
    (net (code "110") (name "3V3") (class "Default")
      (node (ref "C14") (pin "2") (pinfunction "2_2") (pintype "passive"))
      (node (ref "C19") (pin "1") (pinfunction "1_1") (pintype "passive"))
      (node (ref "C25") (pin "2") (pinfunction "2_2") (pintype "passive"))
      (node (ref "C3") (pin "1") (pinfunction "1_1") (pintype "passive"))
      (node (ref "C4") (pin "1") (pinfunction "1_1") (pintype "passive"))
      (node (ref "IC1") (pin "2") (pinfunction "OUT_2") (pintype "passive"))
      (node (ref "IC1") (pin "4") (pinfunction "PAD_4") (pintype "passive"))
      (node (ref "IC2") (pin "8") (pinfunction "VCC_8") (pintype "power_in"))
      (node (ref "R15") (pin "1") (pinfunction "1_1") (pintype "passive"))
      (node (ref "R18") (pin "2") (pinfunction "2_2") (pintype "passive"))
      (node (ref "R19") (pin "1") (pinfunction "1_1") (pintype "passive"))
      (node (ref "R8") (pin "1") (pinfunction "1_1") (pintype "passive"))
      (node (ref "U1") (pin "44") (pinfunction "44_44") (pintype "passive"))
      (node (ref "U1") (pin "7") (pinfunction "7_7") (pintype "passive"))
      (node (ref "U4") (pin "23") (pinfunction "VCCB_23") (pintype "passive"))
      (node (ref "U4") (pin "24") (pinfunction "VCC(B)_24") (pintype "passive"))
      (node (ref "U5") (pin "23") (pinfunction "VCCB_23") (pintype "passive"))
      (node (ref "U5") (pin "24") (pinfunction "VCC(B)_24") (pintype "passive"))
      (node (ref "U6") (pin "23") (pinfunction "VCCB_23") (pintype "passive"))
      (node (ref "U6") (pin "24") (pinfunction "VCC(B)_24") (pintype "passive"))
    )
    (net (code "111") (name "5V") (class "Default")
      (node (ref "C1") (pin "1") (pinfunction "1_1") (pintype "passive"))
      (node (ref "C2") (pin "1") (pinfunction "1_1") (pintype "passive"))
      (node (ref "C24") (pin "1") (pinfunction "1_1") (pintype "passive"))
      (node (ref "C26") (pin "2") (pinfunction "2_2") (pintype "passive"))
      (node (ref "H1") (pin "2") (pinfunction "2_2") (pintype "passive"))
      (node (ref "H2") (pin "2") (pinfunction "2_2") (pintype "passive"))
      (node (ref "H3") (pin "2") (pinfunction "2_2") (pintype "passive"))
      (node (ref "H4") (pin "2") (pinfunction "2_2") (pintype "passive"))
      (node (ref "H5") (pin "2") (pinfunction "2_2") (pintype "passive"))
      (node (ref "H6") (pin "2") (pinfunction "2_2") (pintype "passive"))
      (node (ref "HD1") (pin "2") (pinfunction "2_2") (pintype "passive"))
      (node (ref "HD10") (pin "2") (pinfunction "2_2") (pintype "passive"))
      (node (ref "HD11") (pin "2") (pinfunction "2_2") (pintype "passive"))
      (node (ref "HD4") (pin "1") (pinfunction "1_1") (pintype "passive"))
      (node (ref "HD7") (pin "1") (pinfunction "1_1") (pintype "passive"))
      (node (ref "HD8") (pin "1") (pinfunction "1_1") (pintype "passive"))
      (node (ref "HD9") (pin "1") (pinfunction "1_1") (pintype "passive"))
      (node (ref "IC1") (pin "3") (pinfunction "IN_3") (pintype "passive"))
      (node (ref "R22") (pin "2") (pinfunction "2_2") (pintype "passive"))
      (node (ref "R23") (pin "2") (pinfunction "2_2") (pintype "passive"))
      (node (ref "R24") (pin "2") (pinfunction "2_2") (pintype "passive"))
      (node (ref "R25") (pin "2") (pinfunction "2_2") (pintype "passive"))
      (node (ref "R26") (pin "2") (pinfunction "2_2") (pintype "passive"))
      (node (ref "R27") (pin "2") (pinfunction "2_2") (pintype "passive"))
      (node (ref "R28") (pin "2") (pinfunction "2_2") (pintype "passive"))
      (node (ref "R29") (pin "2") (pinfunction "2_2") (pintype "passive"))
      (node (ref "R7") (pin "1") (pinfunction "1_1") (pintype "passive"))
      (node (ref "U1") (pin "88") (pinfunction "88_88") (pintype "passive"))
      (node (ref "U2") (pin "14") (pinfunction "VCC_14") (pintype "passive"))
      (node (ref "U3") (pin "14") (pinfunction "VCC_14") (pintype "passive"))
      (node (ref "U4") (pin "1") (pinfunction "VCC(A)_1") (pintype "passive"))
      (node (ref "U5") (pin "1") (pinfunction "VCC(A)_1") (pintype "passive"))
      (node (ref "U5") (pin "2") (pinfunction "DIR_2") (pintype "passive"))
      (node (ref "U6") (pin "1") (pinfunction "VCC(A)_1") (pintype "passive"))
      (node (ref "U6") (pin "2") (pinfunction "DIR_2") (pintype "passive"))
    )
    (net (code "112") (name "GND") (class "Default")
      (node (ref "C1") (pin "2") (pinfunction "2_2") (pintype "passive"))
      (node (ref "C10") (pin "1") (pinfunction "1_1") (pintype "passive"))
      (node (ref "C11") (pin "1") (pinfunction "1_1") (pintype "passive"))
      (node (ref "C12") (pin "1") (pinfunction "1_1") (pintype "passive"))
      (node (ref "C13") (pin "2") (pinfunction "2_2") (pintype "passive"))
      (node (ref "C14") (pin "1") (pinfunction "1_1") (pintype "passive"))
      (node (ref "C15") (pin "1") (pinfunction "1_1") (pintype "passive"))
      (node (ref "C16") (pin "1") (pinfunction "1_1") (pintype "passive"))
      (node (ref "C17") (pin "1") (pinfunction "1_1") (pintype "passive"))
      (node (ref "C18") (pin "1") (pinfunction "1_1") (pintype "passive"))
      (node (ref "C19") (pin "2") (pinfunction "2_2") (pintype "passive"))
      (node (ref "C2") (pin "2") (pinfunction "2_2") (pintype "passive"))
      (node (ref "C20") (pin "1") (pinfunction "1_1") (pintype "passive"))
      (node (ref "C21") (pin "1") (pinfunction "1_1") (pintype "passive"))
      (node (ref "C22") (pin "1") (pinfunction "1_1") (pintype "passive"))
      (node (ref "C23") (pin "1") (pinfunction "1_1") (pintype "passive"))
      (node (ref "C24") (pin "2") (pinfunction "2_2") (pintype "passive"))
      (node (ref "C25") (pin "1") (pinfunction "1_1") (pintype "passive"))
      (node (ref "C26") (pin "1") (pinfunction "1_1") (pintype "passive"))
      (node (ref "C3") (pin "2") (pinfunction "2_2") (pintype "passive"))
      (node (ref "C4") (pin "2") (pinfunction "2_2") (pintype "passive"))
      (node (ref "C5") (pin "1") (pinfunction "1_1") (pintype "passive"))
      (node (ref "C6") (pin "1") (pinfunction "1_1") (pintype "passive"))
      (node (ref "C7") (pin "1") (pinfunction "1_1") (pintype "passive"))
      (node (ref "C8") (pin "1") (pinfunction "1_1") (pintype "passive"))
      (node (ref "C9") (pin "1") (pinfunction "1_1") (pintype "passive"))
      (node (ref "D1") (pin "2") (pinfunction "K_2") (pintype "passive"))
      (node (ref "D10") (pin "2") (pinfunction "K_2") (pintype "passive"))
      (node (ref "D2") (pin "2") (pinfunction "K_2") (pintype "passive"))
      (node (ref "D3") (pin "2") (pinfunction "K_2") (pintype "passive"))
      (node (ref "D4") (pin "2") (pinfunction "K_2") (pintype "passive"))
      (node (ref "D5") (pin "2") (pinfunction "K_2") (pintype "passive"))
      (node (ref "D6") (pin "2") (pinfunction "K_2") (pintype "passive"))
      (node (ref "D7") (pin "2") (pinfunction "K_2") (pintype "passive"))
      (node (ref "D8") (pin "2") (pinfunction "K_2") (pintype "passive"))
      (node (ref "D9") (pin "2") (pinfunction "K_2") (pintype "passive"))
      (node (ref "H1") (pin "1") (pinfunction "1_1") (pintype "passive"))
      (node (ref "H2") (pin "1") (pinfunction "1_1") (pintype "passive"))
      (node (ref "H3") (pin "1") (pinfunction "1_1") (pintype "passive"))
      (node (ref "H4") (pin "1") (pinfunction "1_1") (pintype "passive"))
      (node (ref "H5") (pin "1") (pinfunction "1_1") (pintype "passive"))
      (node (ref "H6") (pin "1") (pinfunction "1_1") (pintype "passive"))
      (node (ref "H7") (pin "3") (pinfunction "3_3") (pintype "passive"))
      (node (ref "HD1") (pin "1") (pinfunction "1_1") (pintype "passive"))
      (node (ref "HD4") (pin "4") (pinfunction "4_4") (pintype "passive"))
      (node (ref "HD7") (pin "4") (pinfunction "4_4") (pintype "passive"))
      (node (ref "HD8") (pin "4") (pinfunction "4_4") (pintype "passive"))
      (node (ref "HD9") (pin "4") (pinfunction "4_4") (pintype "passive"))
      (node (ref "IC1") (pin "1") (pinfunction "ADJ/G_1") (pintype "passive"))
      (node (ref "IC2") (pin "1") (pinfunction "A0_1") (pintype "passive"))
      (node (ref "IC2") (pin "2") (pinfunction "A1_2") (pintype "passive"))
      (node (ref "IC2") (pin "3") (pinfunction "A2_3") (pintype "passive"))
      (node (ref "IC2") (pin "4") (pinfunction "GND_4") (pintype "power_in"))
      (node (ref "IC2") (pin "7") (pinfunction "WP_7") (pintype "passive"))
      (node (ref "R10") (pin "2") (pinfunction "2_2") (pintype "passive"))
      (node (ref "R11") (pin "2") (pinfunction "2_2") (pintype "passive"))
      (node (ref "R12") (pin "2") (pinfunction "2_2") (pintype "passive"))
      (node (ref "R14") (pin "2") (pinfunction "2_2") (pintype "passive"))
      (node (ref "R2") (pin "2") (pinfunction "2_2") (pintype "passive"))
      (node (ref "R3") (pin "2") (pinfunction "2_2") (pintype "passive"))
      (node (ref "R4") (pin "1") (pinfunction "1_1") (pintype "passive"))
      (node (ref "R6") (pin "2") (pinfunction "2_2") (pintype "passive"))
      (node (ref "RN1") (pin "1") (pinfunction "1_1") (pintype "passive"))
      (node (ref "RN2") (pin "1") (pinfunction "1_1") (pintype "passive"))
      (node (ref "S1") (pin "1") (pinfunction "1_1") (pintype "passive"))
      (node (ref "U1") (pin "1") (pinfunction "1_1") (pintype "passive"))
      (node (ref "U1") (pin "14") (pinfunction "14_14") (pintype "passive"))
      (node (ref "U1") (pin "31") (pinfunction "31_31") (pintype "passive"))
      (node (ref "U1") (pin "45") (pinfunction "45_45") (pintype "passive"))
      (node (ref "U1") (pin "58") (pinfunction "58_58") (pintype "passive"))
      (node (ref "U1") (pin "75") (pinfunction "75_75") (pintype "passive"))
      (node (ref "U2") (pin "7") (pinfunction "GND_7") (pintype "passive"))
      (node (ref "U3") (pin "7") (pinfunction "GND_7") (pintype "passive"))
      (node (ref "U4") (pin "11") (pinfunction "GND_11") (pintype "passive"))
      (node (ref "U4") (pin "12") (pinfunction "GND_12") (pintype "passive"))
      (node (ref "U4") (pin "13") (pinfunction "GND_13") (pintype "passive"))
      (node (ref "U4") (pin "2") (pinfunction "DIR_2") (pintype "passive"))
      (node (ref "U4") (pin "22") (pinfunction "~{OE}_22") (pintype "passive"))
      (node (ref "U5") (pin "11") (pinfunction "GND_11") (pintype "passive"))
      (node (ref "U5") (pin "12") (pinfunction "GND_12") (pintype "passive"))
      (node (ref "U5") (pin "13") (pinfunction "GND_13") (pintype "passive"))
      (node (ref "U5") (pin "22") (pinfunction "~{OE}_22") (pintype "passive"))
      (node (ref "U6") (pin "11") (pinfunction "GND_11") (pintype "passive"))
      (node (ref "U6") (pin "12") (pinfunction "GND_12") (pintype "passive"))
      (node (ref "U6") (pin "13") (pinfunction "GND_13") (pintype "passive"))
      (node (ref "U6") (pin "22") (pinfunction "~{OE}_22") (pintype "passive"))
    )
    (net (code "113") (name "Net-(D1-A)") (class "Default")
      (node (ref "D1") (pin "1") (pinfunction "A_1") (pintype "passive"))
      (node (ref "R1") (pin "1") (pinfunction "1_1") (pintype "passive"))
    )
    (net (code "114") (name "Net-(D2-A)") (class "Default")
      (node (ref "D2") (pin "1") (pinfunction "A_1") (pintype "passive"))
      (node (ref "R5") (pin "1") (pinfunction "1_1") (pintype "passive"))
    )
    (net (code "115") (name "Net-(D3-A)") (class "Default")
      (node (ref "D3") (pin "1") (pinfunction "A_1") (pintype "passive"))
      (node (ref "R7") (pin "2") (pinfunction "2_2") (pintype "passive"))
    )
    (net (code "116") (name "Net-(D4-A)") (class "Default")
      (node (ref "D4") (pin "1") (pinfunction "A_1") (pintype "passive"))
      (node (ref "R8") (pin "2") (pinfunction "2_2") (pintype "passive"))
    )
    (net (code "117") (name "Net-(D5-A)") (class "Default")
      (node (ref "D5") (pin "1") (pinfunction "A_1") (pintype "passive"))
      (node (ref "R9") (pin "1") (pinfunction "1_1") (pintype "passive"))
    )
    (net (code "118") (name "Net-(D6-A)") (class "Default")
      (node (ref "D6") (pin "1") (pinfunction "A_1") (pintype "passive"))
      (node (ref "R13") (pin "1") (pinfunction "1_1") (pintype "passive"))
    )
    (net (code "119") (name "Net-(D7-A)") (class "Default")
      (node (ref "D7") (pin "1") (pinfunction "A_1") (pintype "passive"))
      (node (ref "R16") (pin "1") (pinfunction "1_1") (pintype "passive"))
    )
    (net (code "120") (name "Net-(D8-A)") (class "Default")
      (node (ref "D8") (pin "1") (pinfunction "A_1") (pintype "passive"))
      (node (ref "R17") (pin "1") (pinfunction "1_1") (pintype "passive"))
    )
    (net (code "121") (name "Net-(D9-A)") (class "Default")
      (node (ref "D9") (pin "1") (pinfunction "A_1") (pintype "passive"))
      (node (ref "R20") (pin "1") (pinfunction "1_1") (pintype "passive"))
    )
    (net (code "122") (name "Net-(D10-A)") (class "Default")
      (node (ref "D10") (pin "1") (pinfunction "A_1") (pintype "passive"))
      (node (ref "R21") (pin "1") (pinfunction "1_1") (pintype "passive"))
    )
    (net (code "123") (name "unconnected-(U1-Pad12)") (class "Default")
      (node (ref "U1") (pin "12") (pinfunction "12_12") (pintype "passive"))
    )
    (net (code "124") (name "unconnected-(U1-Pad52)") (class "Default")
      (node (ref "U1") (pin "52") (pinfunction "52_52") (pintype "passive+no_connect"))
    )
    (net (code "125") (name "unconnected-(U2-7-Pad8)") (class "Default")
      (node (ref "U2") (pin "8") (pinfunction "7_8") (pintype "passive"))
    )
    (net (code "126") (name "unconnected-(U2-8-Pad9)") (class "Default")
      (node (ref "U2") (pin "9") (pinfunction "8_9") (pintype "passive"))
    )
    (net (code "127") (name "unconnected-(U2-Pad5)") (class "Default")
      (node (ref "U2") (pin "5") (pintype "passive"))
    )
    (net (code "128") (name "unconnected-(U2-Pad6)") (class "Default")
      (node (ref "U2") (pin "6") (pintype "passive"))
    )
    (net (code "129") (name "unconnected-(U3-7-Pad8)") (class "Default")
      (node (ref "U3") (pin "8") (pinfunction "7_8") (pintype "passive"))
    )
    (net (code "130") (name "unconnected-(U3-8-Pad9)") (class "Default")
      (node (ref "U3") (pin "9") (pinfunction "8_9") (pintype "passive"))
    )
    (net (code "131") (name "unconnected-(U3-Pad5)") (class "Default")
      (node (ref "U3") (pin "5") (pintype "passive"))
    )
    (net (code "132") (name "unconnected-(U3-Pad6)") (class "Default")
      (node (ref "U3") (pin "6") (pintype "passive"))
    )
  )
)
